# circuit2_ver1.net
KiCad netlist of a schematic drawn in Altium Designer
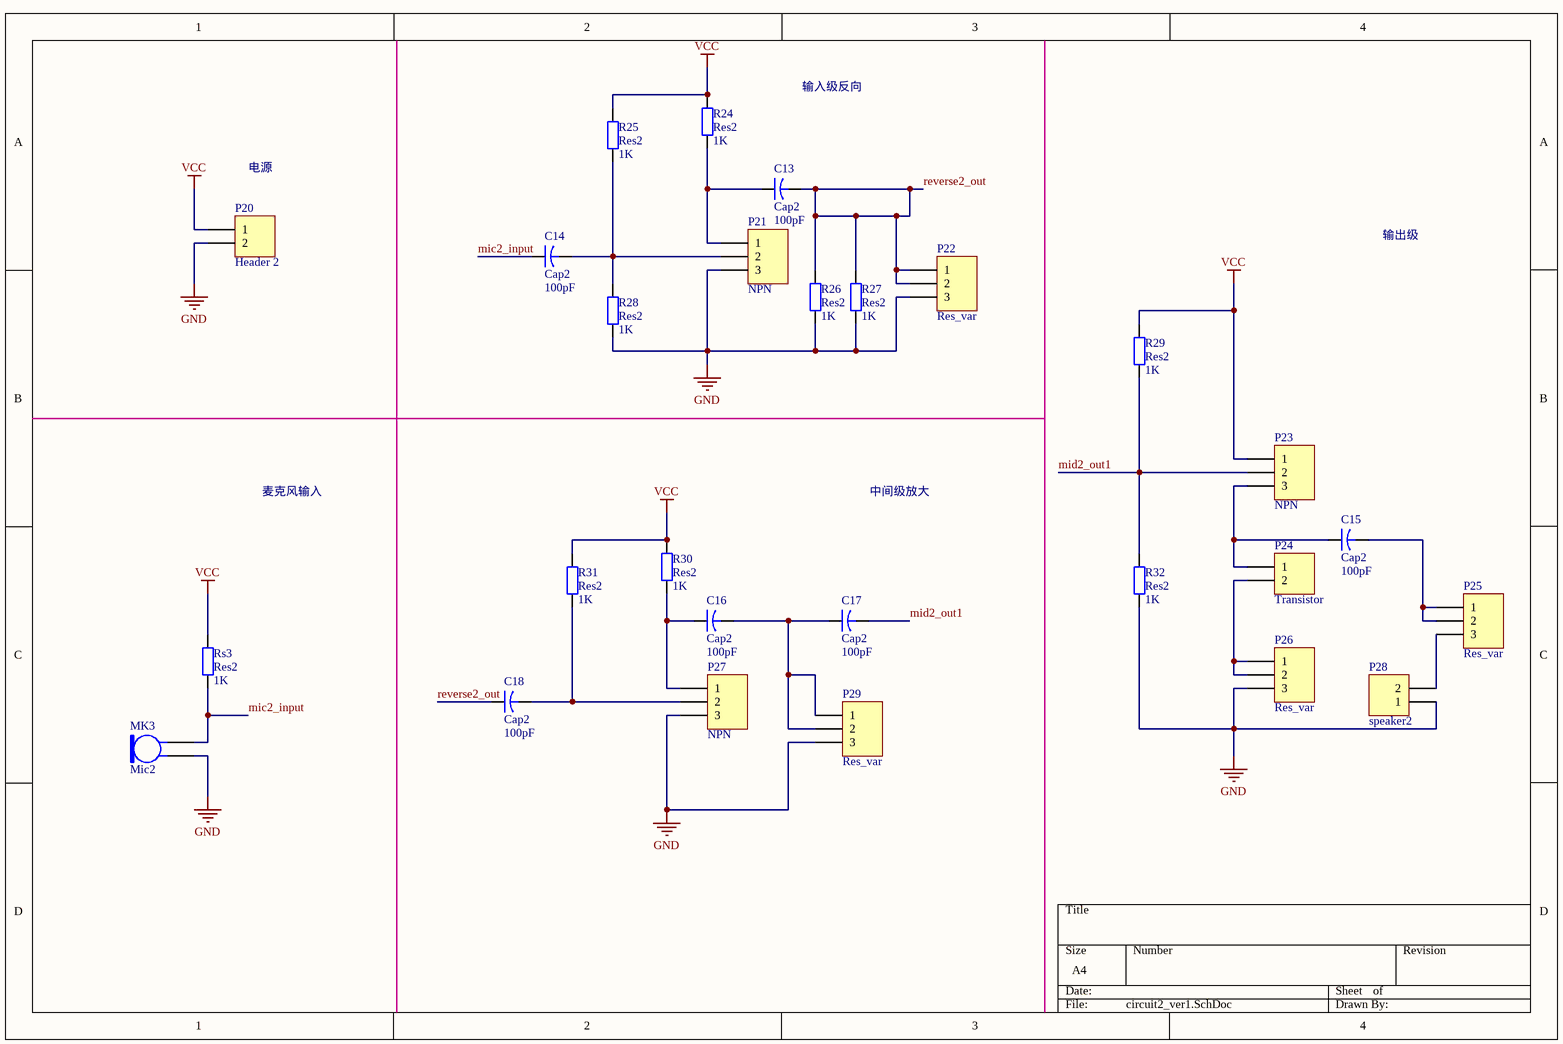
[diagram p0: circuit2_ver1.SchDoc]

(export (version "E")
  (design (tool "Eeschema 10.0.6"))
  (components
    (comp (ref "C13")
      (value "Cap2")
      (footprint "CAPR5-4X5")
      (description "Capacitor")
      (fields (field (name "ALTIUM_VALUE") "100pF") (field (name "PUBLISHER") "Altium Limited"))
      (libsource (lib "Miscellaneous Devices") (part "Cap2"))
    )
    (comp (ref "C14")
      (value "Cap2")
      (footprint "CAPR5-4X5")
      (description "Capacitor")
      (fields (field (name "ALTIUM_VALUE") "100pF") (field (name "PUBLISHER") "Altium Limited"))
      (libsource (lib "Miscellaneous Devices") (part "Cap2"))
    )
    (comp (ref "C15")
      (value "Cap2")
      (footprint "CAPR5-4X5")
      (description "Capacitor")
      (fields (field (name "ALTIUM_VALUE") "100pF") (field (name "PUBLISHER") "Altium Limited"))
      (libsource (lib "Miscellaneous Devices") (part "Cap2"))
    )
    (comp (ref "C16")
      (value "Cap2")
      (footprint "CAPR5-4X5")
      (description "Capacitor")
      (fields (field (name "ALTIUM_VALUE") "100pF") (field (name "PUBLISHER") "Altium Limited"))
      (libsource (lib "Miscellaneous Devices") (part "Cap2"))
    )
    (comp (ref "C17")
      (value "Cap2")
      (footprint "CAPR5-4X5")
      (description "Capacitor")
      (fields (field (name "ALTIUM_VALUE") "100pF") (field (name "PUBLISHER") "Altium Limited"))
      (libsource (lib "Miscellaneous Devices") (part "Cap2"))
    )
    (comp (ref "C18")
      (value "Cap2")
      (footprint "CAPR5-4X5")
      (description "Capacitor")
      (fields (field (name "ALTIUM_VALUE") "100pF") (field (name "PUBLISHER") "Altium Limited"))
      (libsource (lib "Miscellaneous Devices") (part "Cap2"))
    )
    (comp (ref "MK3")
      (value "Mic2")
      (footprint "PIN2")
      (description "Microphone")
      (fields (field (name "PUBLISHER") "Altium Limited"))
      (libsource (lib "Miscellaneous Devices") (part "Mic2"))
    )
    (comp (ref "P20")
      (value "Header 2")
      (footprint "HDR1X2")
      (description "Header, 2-Pin")
      (fields (field (name "PUBLISHER") "Altium Limited"))
      (libsource (lib "Miscellaneous Connectors") (part "Header 2"))
    )
    (comp (ref "P21")
      (value "NPN")
      (footprint "HDR1X3")
      (description "Header, 3-Pin")
      (fields (field (name "PUBLISHER") "Altium Limited"))
      (libsource (lib "Miscellaneous Connectors") (part "Header 3"))
    )
    (comp (ref "P22")
      (value "Res_var")
      (footprint "HDR1X3")
      (description "Header, 3-Pin")
      (fields (field (name "PUBLISHER") "Altium Limited"))
      (libsource (lib "Miscellaneous Connectors") (part "Header 3"))
    )
    (comp (ref "P23")
      (value "NPN")
      (footprint "HDR1X3")
      (description "Header, 3-Pin")
      (fields (field (name "PUBLISHER") "Altium Limited"))
      (libsource (lib "Miscellaneous Connectors") (part "Header 3"))
    )
    (comp (ref "P24")
      (value "Transistor")
      (footprint "HDR1X2")
      (description "Header, 2-Pin")
      (fields (field (name "PUBLISHER") "Altium Limited"))
      (libsource (lib "Miscellaneous Connectors") (part "Header 2"))
    )
    (comp (ref "P25")
      (value "Res_var")
      (footprint "HDR1X3")
      (description "Header, 3-Pin")
      (fields (field (name "PUBLISHER") "Altium Limited"))
      (libsource (lib "Miscellaneous Connectors") (part "Header 3"))
    )
    (comp (ref "P26")
      (value "Res_var")
      (footprint "HDR1X3")
      (description "Header, 3-Pin")
      (fields (field (name "PUBLISHER") "Altium Limited"))
      (libsource (lib "Miscellaneous Connectors") (part "Header 3"))
    )
    (comp (ref "P27")
      (value "NPN")
      (footprint "HDR1X3")
      (description "Header, 3-Pin")
      (fields (field (name "PUBLISHER") "Altium Limited"))
      (libsource (lib "Miscellaneous Connectors") (part "Header 3"))
    )
    (comp (ref "P28")
      (value "speaker2")
      (footprint "HDR1X2")
      (description "Header, 2-Pin")
      (fields (field (name "PUBLISHER") "Altium Limited"))
      (libsource (lib "") (part "Header 2_1"))
    )
    (comp (ref "P29")
      (value "Res_var")
      (footprint "HDR1X3")
      (description "Header, 3-Pin")
      (fields (field (name "PUBLISHER") "Altium Limited"))
      (libsource (lib "Miscellaneous Connectors") (part "Header 3"))
    )
    (comp (ref "R24")
      (value "Res2")
      (footprint "AXIAL-0.4")
      (description "Resistor")
      (fields (field (name "ALTIUM_VALUE") "1K") (field (name "PUBLISHER") "Altium Limited"))
      (libsource (lib "Miscellaneous Devices") (part "Res2"))
    )
    (comp (ref "R25")
      (value "Res2")
      (footprint "AXIAL-0.4")
      (description "Resistor")
      (fields (field (name "ALTIUM_VALUE") "1K") (field (name "PUBLISHER") "Altium Limited"))
      (libsource (lib "Miscellaneous Devices") (part "Res2"))
    )
    (comp (ref "R26")
      (value "Res2")
      (footprint "AXIAL-0.4")
      (description "Resistor")
      (fields (field (name "ALTIUM_VALUE") "1K") (field (name "PUBLISHER") "Altium Limited"))
      (libsource (lib "Miscellaneous Devices") (part "Res2"))
    )
    (comp (ref "R27")
      (value "Res2")
      (footprint "AXIAL-0.4")
      (description "Resistor")
      (fields (field (name "ALTIUM_VALUE") "1K") (field (name "PUBLISHER") "Altium Limited"))
      (libsource (lib "Miscellaneous Devices") (part "Res2"))
    )
    (comp (ref "R28")
      (value "Res2")
      (footprint "AXIAL-0.4")
      (description "Resistor")
      (fields (field (name "ALTIUM_VALUE") "1K") (field (name "PUBLISHER") "Altium Limited"))
      (libsource (lib "Miscellaneous Devices") (part "Res2"))
    )
    (comp (ref "R29")
      (value "Res2")
      (footprint "AXIAL-0.4")
      (description "Resistor")
      (fields (field (name "ALTIUM_VALUE") "1K") (field (name "PUBLISHER") "Altium Limited"))
      (libsource (lib "Miscellaneous Devices") (part "Res2"))
    )
    (comp (ref "R30")
      (value "Res2")
      (footprint "AXIAL-0.4")
      (description "Resistor")
      (fields (field (name "ALTIUM_VALUE") "1K") (field (name "PUBLISHER") "Altium Limited"))
      (libsource (lib "Miscellaneous Devices") (part "Res2"))
    )
    (comp (ref "R31")
      (value "Res2")
      (footprint "AXIAL-0.4")
      (description "Resistor")
      (fields (field (name "ALTIUM_VALUE") "1K") (field (name "PUBLISHER") "Altium Limited"))
      (libsource (lib "Miscellaneous Devices") (part "Res2"))
    )
    (comp (ref "R32")
      (value "Res2")
      (footprint "AXIAL-0.4")
      (description "Resistor")
      (fields (field (name "ALTIUM_VALUE") "1K") (field (name "PUBLISHER") "Altium Limited"))
      (libsource (lib "Miscellaneous Devices") (part "Res2"))
    )
    (comp (ref "Rs3")
      (value "Res2")
      (footprint "AXIAL-0.4")
      (description "Resistor")
      (fields (field (name "ALTIUM_VALUE") "1K") (field (name "PUBLISHER") "Altium Limited"))
      (libsource (lib "Miscellaneous Devices") (part "Res2"))
    )
  )
  (nets
    (net (code "1") (name "/mic2_input") (class "Default")
      (node (ref "C14") (pin "1") (pinfunction "1_1") (pintype "passive"))
      (node (ref "MK3") (pin "2") (pinfunction "2_2") (pintype "passive"))
      (node (ref "Rs3") (pin "1") (pinfunction "1_1") (pintype "passive"))
    )
    (net (code "2") (name "/mid2_out1") (class "Default")
      (node (ref "C17") (pin "2") (pinfunction "2_2") (pintype "passive"))
      (node (ref "P23") (pin "2") (pinfunction "2_2") (pintype "passive"))
      (node (ref "R29") (pin "1") (pinfunction "1_1") (pintype "passive"))
      (node (ref "R32") (pin "2") (pinfunction "2_2") (pintype "passive"))
    )
    (net (code "3") (name "/reverse2_out") (class "Default")
      (node (ref "C13") (pin "2") (pinfunction "2_2") (pintype "passive"))
      (node (ref "C18") (pin "1") (pinfunction "1_1") (pintype "passive"))
      (node (ref "P22") (pin "1") (pinfunction "1_1") (pintype "passive"))
      (node (ref "P22") (pin "2") (pinfunction "2_2") (pintype "passive"))
      (node (ref "R26") (pin "2") (pinfunction "2_2") (pintype "passive"))
      (node (ref "R27") (pin "2") (pinfunction "2_2") (pintype "passive"))
    )
    (net (code "4") (name "GND") (class "Default")
      (node (ref "MK3") (pin "1") (pinfunction "1_1") (pintype "passive"))
      (node (ref "P20") (pin "2") (pinfunction "2_2") (pintype "passive"))
      (node (ref "P21") (pin "3") (pinfunction "3_3") (pintype "passive"))
      (node (ref "P22") (pin "3") (pinfunction "3_3") (pintype "passive"))
      (node (ref "P26") (pin "3") (pinfunction "3_3") (pintype "passive"))
      (node (ref "P27") (pin "3") (pinfunction "3_3") (pintype "passive"))
      (node (ref "P28") (pin "1") (pinfunction "1_1") (pintype "passive"))
      (node (ref "P29") (pin "3") (pinfunction "3_3") (pintype "passive"))
      (node (ref "R26") (pin "1") (pinfunction "1_1") (pintype "passive"))
      (node (ref "R27") (pin "1") (pinfunction "1_1") (pintype "passive"))
      (node (ref "R28") (pin "1") (pinfunction "1_1") (pintype "passive"))
      (node (ref "R32") (pin "1") (pinfunction "1_1") (pintype "passive"))
    )
    (net (code "5") (name "Net-(C13-Pad1)") (class "Default")
      (node (ref "C13") (pin "1") (pinfunction "1_1") (pintype "passive"))
      (node (ref "P21") (pin "1") (pinfunction "1_1") (pintype "passive"))
      (node (ref "R24") (pin "1") (pinfunction "1_1") (pintype "passive"))
    )
    (net (code "6") (name "Net-(C14-Pad2)") (class "Default")
      (node (ref "C14") (pin "2") (pinfunction "2_2") (pintype "passive"))
      (node (ref "P21") (pin "2") (pinfunction "2_2") (pintype "passive"))
      (node (ref "R25") (pin "1") (pinfunction "1_1") (pintype "passive"))
      (node (ref "R28") (pin "2") (pinfunction "2_2") (pintype "passive"))
    )
    (net (code "7") (name "Net-(C15-Pad1)") (class "Default")
      (node (ref "C15") (pin "1") (pinfunction "1_1") (pintype "passive"))
      (node (ref "P23") (pin "3") (pinfunction "3_3") (pintype "passive"))
      (node (ref "P24") (pin "1") (pinfunction "1_1") (pintype "passive"))
    )
    (net (code "8") (name "Net-(C15-Pad2)") (class "Default")
      (node (ref "C15") (pin "2") (pinfunction "2_2") (pintype "passive"))
      (node (ref "P25") (pin "1") (pinfunction "1_1") (pintype "passive"))
      (node (ref "P25") (pin "2") (pinfunction "2_2") (pintype "passive"))
    )
    (net (code "9") (name "Net-(C16-Pad1)") (class "Default")
      (node (ref "C16") (pin "1") (pinfunction "1_1") (pintype "passive"))
      (node (ref "P27") (pin "1") (pinfunction "1_1") (pintype "passive"))
      (node (ref "R30") (pin "1") (pinfunction "1_1") (pintype "passive"))
    )
    (net (code "10") (name "Net-(C16-Pad2)") (class "Default")
      (node (ref "C16") (pin "2") (pinfunction "2_2") (pintype "passive"))
      (node (ref "C17") (pin "1") (pinfunction "1_1") (pintype "passive"))
      (node (ref "P29") (pin "1") (pinfunction "1_1") (pintype "passive"))
      (node (ref "P29") (pin "2") (pinfunction "2_2") (pintype "passive"))
    )
    (net (code "11") (name "Net-(C18-Pad2)") (class "Default")
      (node (ref "C18") (pin "2") (pinfunction "2_2") (pintype "passive"))
      (node (ref "P27") (pin "2") (pinfunction "2_2") (pintype "passive"))
      (node (ref "R31") (pin "1") (pinfunction "1_1") (pintype "passive"))
    )
    (net (code "12") (name "Net-(P24-Pad2)") (class "Default")
      (node (ref "P24") (pin "2") (pinfunction "2_2") (pintype "passive"))
      (node (ref "P26") (pin "1") (pinfunction "1_1") (pintype "passive"))
      (node (ref "P26") (pin "2") (pinfunction "2_2") (pintype "passive"))
    )
    (net (code "13") (name "Net-(P25-Pad3)") (class "Default")
      (node (ref "P25") (pin "3") (pinfunction "3_3") (pintype "passive"))
      (node (ref "P28") (pin "2") (pinfunction "2_2") (pintype "passive"))
    )
    (net (code "14") (name "VCC") (class "Default")
      (node (ref "P20") (pin "1") (pinfunction "1_1") (pintype "passive"))
      (node (ref "P23") (pin "1") (pinfunction "1_1") (pintype "passive"))
      (node (ref "R24") (pin "2") (pinfunction "2_2") (pintype "passive"))
      (node (ref "R25") (pin "2") (pinfunction "2_2") (pintype "passive"))
      (node (ref "R29") (pin "2") (pinfunction "2_2") (pintype "passive"))
      (node (ref "R30") (pin "2") (pinfunction "2_2") (pintype "passive"))
      (node (ref "R31") (pin "2") (pinfunction "2_2") (pintype "passive"))
      (node (ref "Rs3") (pin "2") (pinfunction "2_2") (pintype "passive"))
    )
  )
)
